# ledshield_v2.net
KiCad netlist of a schematic drawn in EAGLE
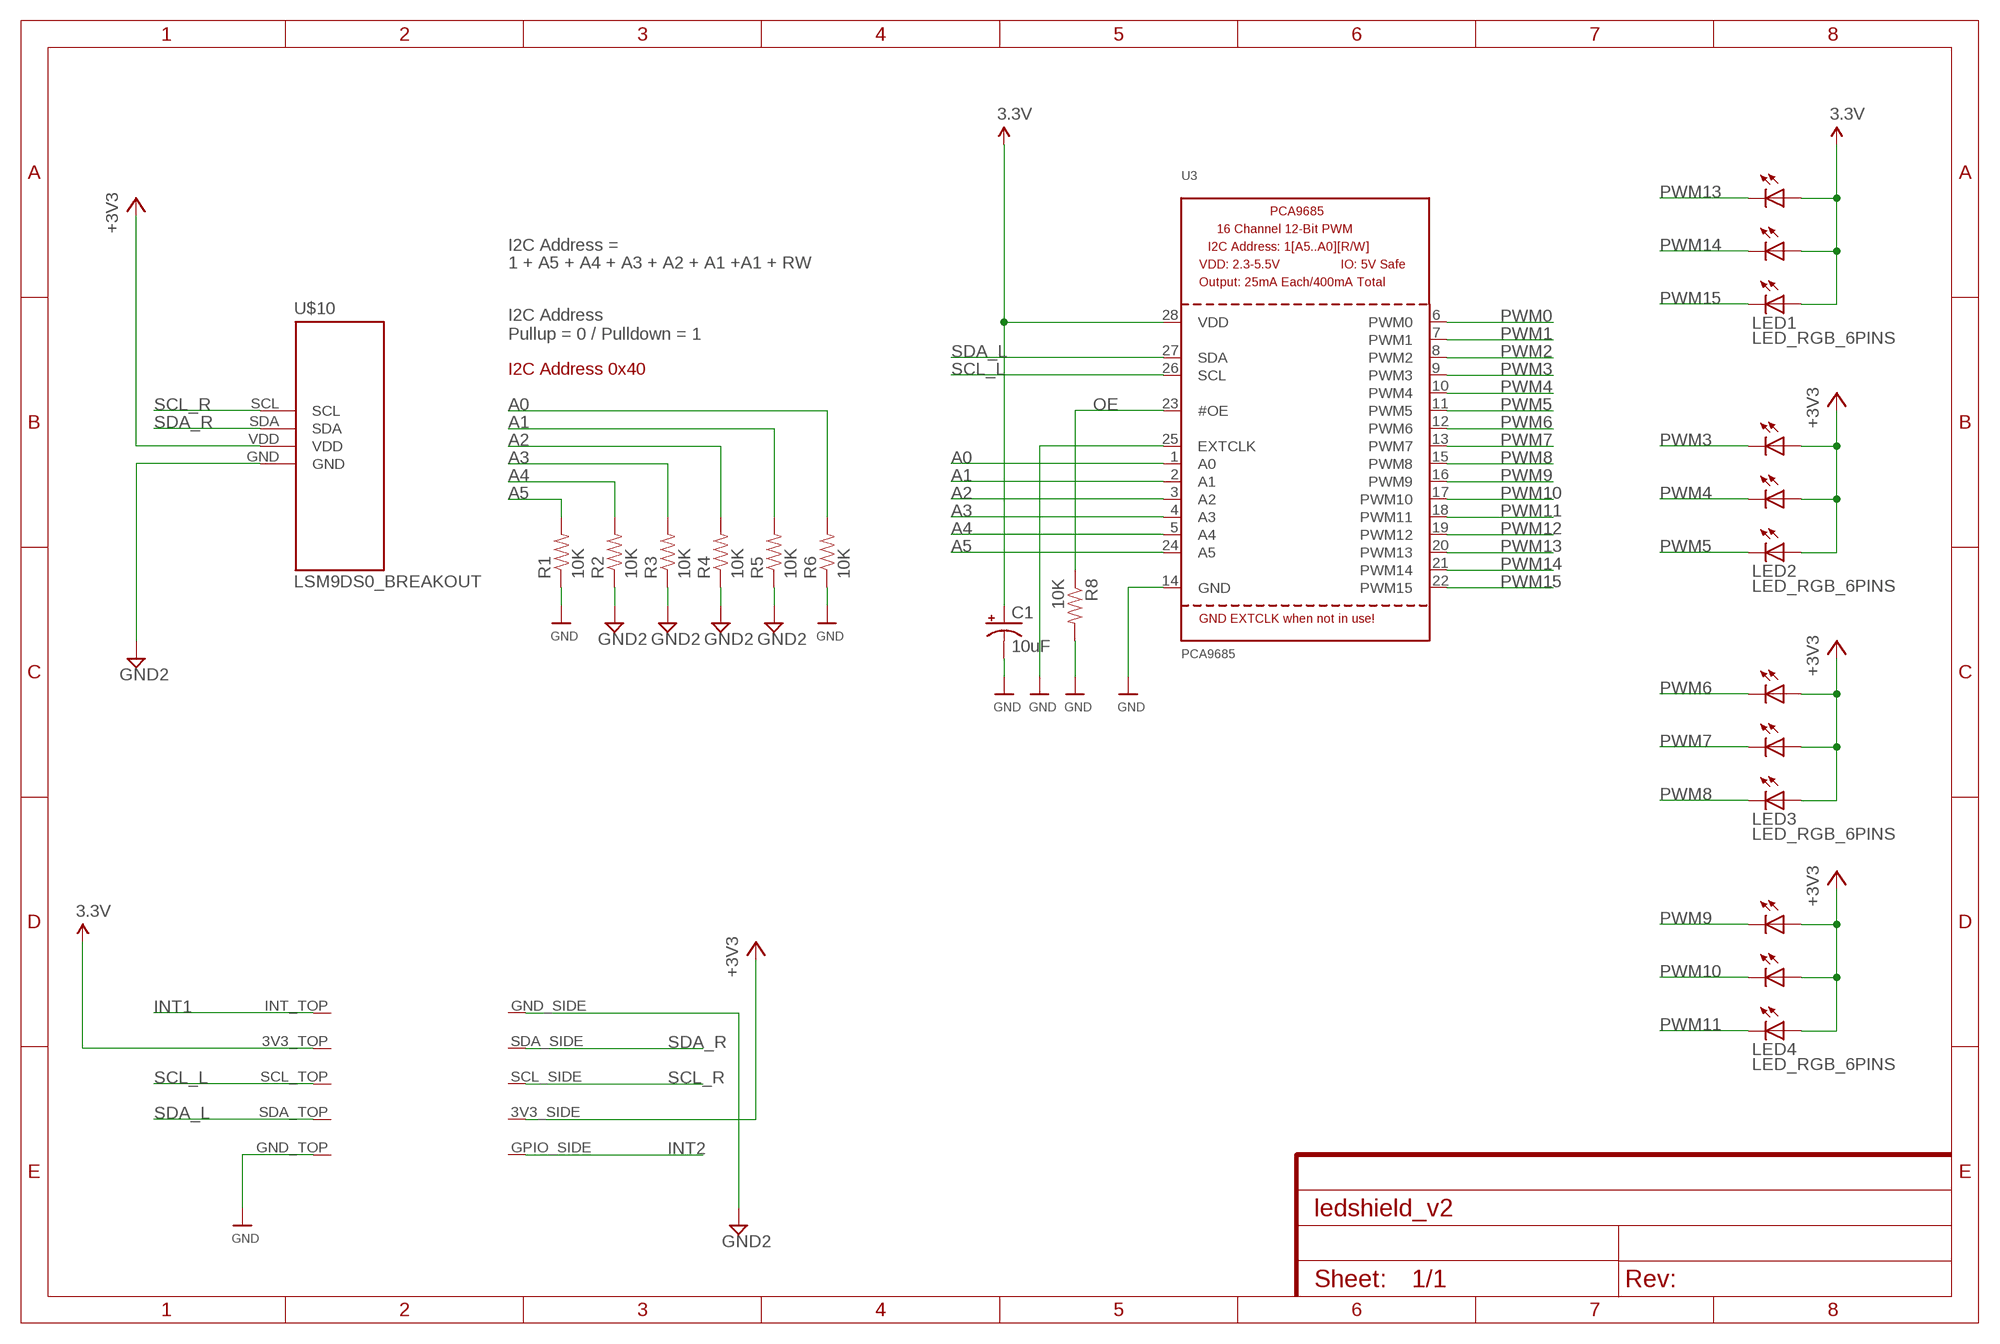
[diagram p0: schematic, sheet 1]

(export (version "E")
  (design (tool "Eeschema 10.0.6"))
  (components
    (comp (ref "C1")
      (value "10uF")
      (footprint "eagle-import:EIA3216")
      (libsource (lib "eagle-import") (part "CAP_POL1206"))
    )
    (comp (ref "LED1")
      (value "LED_RGB_6PINS")
      (footprint "eagle-import:LED_RGB_6PINS")
      (libsource (lib "eagle-import") (part "LED_RGB_6PINS"))
    )
    (comp (ref "LED2")
      (value "LED_RGB_6PINS")
      (footprint "eagle-import:LED_RGB_6PINS")
      (libsource (lib "eagle-import") (part "LED_RGB_6PINS"))
    )
    (comp (ref "LED3")
      (value "LED_RGB_6PINS")
      (footprint "eagle-import:LED_RGB_6PINS")
      (libsource (lib "eagle-import") (part "LED_RGB_6PINS"))
    )
    (comp (ref "LED4")
      (value "LED_RGB_6PINS")
      (footprint "eagle-import:LED_RGB_6PINS")
      (libsource (lib "eagle-import") (part "LED_RGB_6PINS"))
    )
    (comp (ref "R1")
      (value "10K")
      (footprint "eagle-import:1206")
      (libsource (lib "eagle-import") (part "RESISTOR1206"))
    )
    (comp (ref "R2")
      (value "10K")
      (footprint "eagle-import:1206")
      (libsource (lib "eagle-import") (part "RESISTOR1206"))
    )
    (comp (ref "R3")
      (value "10K")
      (footprint "eagle-import:1206")
      (libsource (lib "eagle-import") (part "RESISTOR1206"))
    )
    (comp (ref "R4")
      (value "10K")
      (footprint "eagle-import:1206")
      (libsource (lib "eagle-import") (part "RESISTOR1206"))
    )
    (comp (ref "R5")
      (value "10K")
      (footprint "eagle-import:1206")
      (libsource (lib "eagle-import") (part "RESISTOR1206"))
    )
    (comp (ref "R6")
      (value "10K")
      (footprint "eagle-import:1206")
      (libsource (lib "eagle-import") (part "RESISTOR1206"))
    )
    (comp (ref "R8")
      (value "10K")
      (footprint "eagle-import:1206")
      (libsource (lib "eagle-import") (part "RESISTOR1206"))
    )
    (comp (ref "U$1")
      (value "IOT_MODULE_MAIN_V2_PTH")
      (footprint "eagle-import:IOT_MODULE_MAIN_V3_PTH")
      (libsource (lib "eagle-import") (part "IOT_MODULE_MAIN_V2_PTH"))
    )
    (comp (ref "U$10")
      (value "LSM9DS0_BREAKOUT")
      (footprint "eagle-import:LSM9DS0_BREAKOUT")
      (libsource (lib "eagle-import") (part "LSM9DS0_BREAKOUT"))
    )
    (comp (ref "U3")
      (value "PCA9685")
      (footprint "eagle-import:TSSOP28")
      (libsource (lib "eagle-import") (part "PCA9685"))
    )
  )
  (nets
    (net (code "1") (name "+3V3") (class "Default")
      (node (ref "LED2") (pin "BA") (pinfunction "BA_BA") (pintype "passive"))
      (node (ref "LED2") (pin "GA") (pinfunction "GA_GA") (pintype "passive"))
      (node (ref "LED2") (pin "RA") (pinfunction "RA_RA") (pintype "passive"))
      (node (ref "LED3") (pin "BA") (pinfunction "BA_BA") (pintype "passive"))
      (node (ref "LED3") (pin "GA") (pinfunction "GA_GA") (pintype "passive"))
      (node (ref "LED3") (pin "RA") (pinfunction "RA_RA") (pintype "passive"))
      (node (ref "LED4") (pin "BA") (pinfunction "BA_BA") (pintype "passive"))
      (node (ref "LED4") (pin "GA") (pinfunction "GA_GA") (pintype "passive"))
      (node (ref "LED4") (pin "RA") (pinfunction "RA_RA") (pintype "passive"))
      (node (ref "U$1") (pin "3V3_SIDE") (pinfunction "3V3_SIDE_3V3_SIDE") (pintype "bidirectional"))
      (node (ref "U$10") (pin "VDD") (pinfunction "VDD_VDD") (pintype "power_in"))
    )
    (net (code "2") (name "/A0") (class "Default")
      (node (ref "R6") (pin "2") (pinfunction "2_2") (pintype "passive"))
      (node (ref "U3") (pin "1") (pinfunction "A0_1") (pintype "bidirectional"))
    )
    (net (code "3") (name "/A1") (class "Default")
      (node (ref "R5") (pin "2") (pinfunction "2_2") (pintype "passive"))
      (node (ref "U3") (pin "2") (pinfunction "A1_2") (pintype "bidirectional"))
    )
    (net (code "4") (name "/A2") (class "Default")
      (node (ref "R4") (pin "2") (pinfunction "2_2") (pintype "passive"))
      (node (ref "U3") (pin "3") (pinfunction "A2_3") (pintype "bidirectional"))
    )
    (net (code "5") (name "/A3") (class "Default")
      (node (ref "R3") (pin "2") (pinfunction "2_2") (pintype "passive"))
      (node (ref "U3") (pin "4") (pinfunction "A3_4") (pintype "bidirectional"))
    )
    (net (code "6") (name "/A4") (class "Default")
      (node (ref "R2") (pin "2") (pinfunction "2_2") (pintype "passive"))
      (node (ref "U3") (pin "5") (pinfunction "A4_5") (pintype "bidirectional"))
    )
    (net (code "7") (name "/A5") (class "Default")
      (node (ref "R1") (pin "2") (pinfunction "2_2") (pintype "passive"))
      (node (ref "U3") (pin "24") (pinfunction "A5_24") (pintype "bidirectional"))
    )
    (net (code "8") (name "/INT1") (class "Default")
      (node (ref "U$1") (pin "INT_TOP") (pinfunction "INT_TOP_INT_TOP") (pintype "bidirectional"))
    )
    (net (code "9") (name "/INT2") (class "Default")
      (node (ref "U$1") (pin "GPIO_SIDE") (pinfunction "GPIO_SIDE_GPIO_SIDE") (pintype "bidirectional"))
    )
    (net (code "10") (name "/OE") (class "Default")
      (node (ref "R8") (pin "1") (pinfunction "1_1") (pintype "passive"))
      (node (ref "U3") (pin "23") (pinfunction "#OE_23") (pintype "input"))
    )
    (net (code "11") (name "/PWM0") (class "Default")
      (node (ref "U3") (pin "6") (pinfunction "PWM0_6") (pintype "output"))
    )
    (net (code "12") (name "/PWM1") (class "Default")
      (node (ref "U3") (pin "7") (pinfunction "PWM1_7") (pintype "output"))
    )
    (net (code "13") (name "/PWM2") (class "Default")
      (node (ref "U3") (pin "8") (pinfunction "PWM2_8") (pintype "output"))
    )
    (net (code "14") (name "/PWM3") (class "Default")
      (node (ref "LED2") (pin "BC") (pinfunction "BC_BC") (pintype "passive"))
      (node (ref "U3") (pin "9") (pinfunction "PWM3_9") (pintype "output"))
    )
    (net (code "15") (name "/PWM4") (class "Default")
      (node (ref "LED2") (pin "RC") (pinfunction "RC_RC") (pintype "passive"))
      (node (ref "U3") (pin "10") (pinfunction "PWM4_10") (pintype "output"))
    )
    (net (code "16") (name "/PWM5") (class "Default")
      (node (ref "LED2") (pin "GC") (pinfunction "GC_GC") (pintype "passive"))
      (node (ref "U3") (pin "11") (pinfunction "PWM5_11") (pintype "output"))
    )
    (net (code "17") (name "/PWM6") (class "Default")
      (node (ref "LED3") (pin "BC") (pinfunction "BC_BC") (pintype "passive"))
      (node (ref "U3") (pin "12") (pinfunction "PWM6_12") (pintype "output"))
    )
    (net (code "18") (name "/PWM7") (class "Default")
      (node (ref "LED3") (pin "RC") (pinfunction "RC_RC") (pintype "passive"))
      (node (ref "U3") (pin "13") (pinfunction "PWM7_13") (pintype "output"))
    )
    (net (code "19") (name "/PWM8") (class "Default")
      (node (ref "LED3") (pin "GC") (pinfunction "GC_GC") (pintype "passive"))
      (node (ref "U3") (pin "15") (pinfunction "PWM8_15") (pintype "output"))
    )
    (net (code "20") (name "/PWM9") (class "Default")
      (node (ref "LED4") (pin "BC") (pinfunction "BC_BC") (pintype "passive"))
      (node (ref "U3") (pin "16") (pinfunction "PWM9_16") (pintype "output"))
    )
    (net (code "21") (name "/PWM10") (class "Default")
      (node (ref "LED4") (pin "RC") (pinfunction "RC_RC") (pintype "passive"))
      (node (ref "U3") (pin "17") (pinfunction "PWM10_17") (pintype "output"))
    )
    (net (code "22") (name "/PWM11") (class "Default")
      (node (ref "LED4") (pin "GC") (pinfunction "GC_GC") (pintype "passive"))
      (node (ref "U3") (pin "18") (pinfunction "PWM11_18") (pintype "output"))
    )
    (net (code "23") (name "/PWM12") (class "Default")
      (node (ref "U3") (pin "19") (pinfunction "PWM12_19") (pintype "output"))
    )
    (net (code "24") (name "/PWM13") (class "Default")
      (node (ref "LED1") (pin "BC") (pinfunction "BC_BC") (pintype "passive"))
      (node (ref "U3") (pin "20") (pinfunction "PWM13_20") (pintype "output"))
    )
    (net (code "25") (name "/PWM14") (class "Default")
      (node (ref "LED1") (pin "RC") (pinfunction "RC_RC") (pintype "passive"))
      (node (ref "U3") (pin "21") (pinfunction "PWM14_21") (pintype "output"))
    )
    (net (code "26") (name "/PWM15") (class "Default")
      (node (ref "LED1") (pin "GC") (pinfunction "GC_GC") (pintype "passive"))
      (node (ref "U3") (pin "22") (pinfunction "PWM15_22") (pintype "output"))
    )
    (net (code "27") (name "/SCL_L") (class "Default")
      (node (ref "U$1") (pin "SCL_TOP") (pinfunction "SCL_TOP_SCL_TOP") (pintype "bidirectional"))
      (node (ref "U3") (pin "26") (pinfunction "SCL_26") (pintype "bidirectional"))
    )
    (net (code "28") (name "/SCL_R") (class "Default")
      (node (ref "U$1") (pin "SCL_SIDE") (pinfunction "SCL_SIDE_SCL_SIDE") (pintype "bidirectional"))
      (node (ref "U$10") (pin "SCL") (pinfunction "SCL_SCL") (pintype "bidirectional"))
    )
    (net (code "29") (name "/SDA_L") (class "Default")
      (node (ref "U$1") (pin "SDA_TOP") (pinfunction "SDA_TOP_SDA_TOP") (pintype "bidirectional"))
      (node (ref "U3") (pin "27") (pinfunction "SDA_27") (pintype "bidirectional"))
    )
    (net (code "30") (name "/SDA_R") (class "Default")
      (node (ref "U$1") (pin "SDA_SIDE") (pinfunction "SDA_SIDE_SDA_SIDE") (pintype "bidirectional"))
      (node (ref "U$10") (pin "SDA") (pinfunction "SDA_SDA") (pintype "bidirectional"))
    )
    (net (code "31") (name "3.3V") (class "Default")
      (node (ref "C1") (pin "A") (pinfunction "+_A") (pintype "passive"))
      (node (ref "LED1") (pin "BA") (pinfunction "BA_BA") (pintype "passive"))
      (node (ref "LED1") (pin "GA") (pinfunction "GA_GA") (pintype "passive"))
      (node (ref "LED1") (pin "RA") (pinfunction "RA_RA") (pintype "passive"))
      (node (ref "U$1") (pin "3V3_TOP") (pinfunction "3V3_TOP_3V3_TOP") (pintype "bidirectional"))
      (node (ref "U3") (pin "28") (pinfunction "VDD_28") (pintype "power_in"))
    )
    (net (code "32") (name "GND") (class "Default")
      (node (ref "C1") (pin "C") (pinfunction "-_C") (pintype "passive"))
      (node (ref "R1") (pin "1") (pinfunction "1_1") (pintype "passive"))
      (node (ref "R6") (pin "1") (pinfunction "1_1") (pintype "passive"))
      (node (ref "R8") (pin "2") (pinfunction "2_2") (pintype "passive"))
      (node (ref "U$1") (pin "GND_TOP") (pinfunction "GND_TOP_GND_TOP") (pintype "bidirectional"))
      (node (ref "U3") (pin "14") (pinfunction "GND_14") (pintype "power_in"))
      (node (ref "U3") (pin "25") (pinfunction "EXTCLK_25") (pintype "input"))
    )
    (net (code "33") (name "GND2") (class "Default")
      (node (ref "R2") (pin "1") (pinfunction "1_1") (pintype "passive"))
      (node (ref "R3") (pin "1") (pinfunction "1_1") (pintype "passive"))
      (node (ref "R4") (pin "1") (pinfunction "1_1") (pintype "passive"))
      (node (ref "R5") (pin "1") (pinfunction "1_1") (pintype "passive"))
      (node (ref "U$1") (pin "GND_SIDE") (pinfunction "GND_SIDE_GND_SIDE") (pintype "bidirectional"))
      (node (ref "U$10") (pin "GND") (pinfunction "GND_GND") (pintype "power_in"))
    )
  )
)
